# Driver4portas.net
KiCad netlist of a schematic drawn in EAGLE
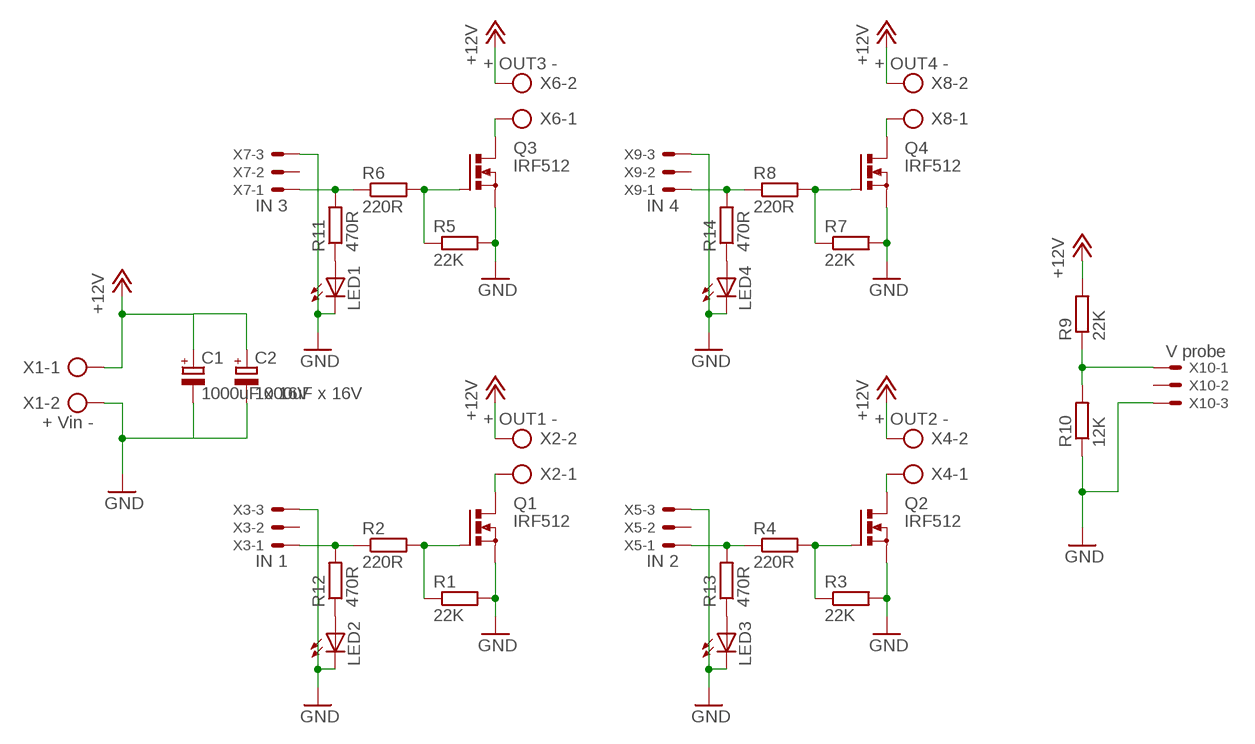
[diagram p0: schematic, sheet 1]

(export (version "E")
  (design (tool "Eeschema 10.0.6"))
  (components
    (comp (ref "C1")
      (value "1000uF x 16V")
      (footprint "eagle-import:E2,5-7")
      (libsource (lib "eagle-import") (part "CPOL-EUE2.5-7"))
    )
    (comp (ref "C2")
      (value "1000uF x 16V")
      (footprint "eagle-import:E2,5-7")
      (libsource (lib "eagle-import") (part "CPOL-EUE2.5-7"))
    )
    (comp (ref "LED1")
      (value "LED3MM")
      (footprint "eagle-import:LED3MM")
      (libsource (lib "eagle-import") (part "LED3MM"))
    )
    (comp (ref "LED2")
      (value "LED3MM")
      (footprint "eagle-import:LED3MM")
      (libsource (lib "eagle-import") (part "LED3MM"))
    )
    (comp (ref "LED3")
      (value "LED3MM")
      (footprint "eagle-import:LED3MM")
      (libsource (lib "eagle-import") (part "LED3MM"))
    )
    (comp (ref "LED4")
      (value "LED3MM")
      (footprint "eagle-import:LED3MM")
      (libsource (lib "eagle-import") (part "LED3MM"))
    )
    (comp (ref "Q1")
      (value "IRF512")
      (footprint "eagle-import:TO220BV")
      (libsource (lib "eagle-import") (part "IRF512"))
    )
    (comp (ref "Q2")
      (value "IRF512")
      (footprint "eagle-import:TO220BV")
      (libsource (lib "eagle-import") (part "IRF512"))
    )
    (comp (ref "Q3")
      (value "IRF512")
      (footprint "eagle-import:TO220BV")
      (libsource (lib "eagle-import") (part "IRF512"))
    )
    (comp (ref "Q4")
      (value "IRF512")
      (footprint "eagle-import:TO220BV")
      (libsource (lib "eagle-import") (part "IRF512"))
    )
    (comp (ref "R1")
      (value "22K")
      (footprint "eagle-import:0204_7")
      (libsource (lib "eagle-import") (part "R-EU_0204/7"))
    )
    (comp (ref "R2")
      (value "220R")
      (footprint "eagle-import:0204_7")
      (libsource (lib "eagle-import") (part "R-EU_0204/7"))
    )
    (comp (ref "R3")
      (value "22K")
      (footprint "eagle-import:0204_7")
      (libsource (lib "eagle-import") (part "R-EU_0204/7"))
    )
    (comp (ref "R4")
      (value "220R")
      (footprint "eagle-import:0204_7")
      (libsource (lib "eagle-import") (part "R-EU_0204/7"))
    )
    (comp (ref "R5")
      (value "22K")
      (footprint "eagle-import:0204_7")
      (libsource (lib "eagle-import") (part "R-EU_0204/7"))
    )
    (comp (ref "R6")
      (value "220R")
      (footprint "eagle-import:0204_7")
      (libsource (lib "eagle-import") (part "R-EU_0204/7"))
    )
    (comp (ref "R7")
      (value "22K")
      (footprint "eagle-import:0204_7")
      (libsource (lib "eagle-import") (part "R-EU_0204/7"))
    )
    (comp (ref "R8")
      (value "220R")
      (footprint "eagle-import:0204_7")
      (libsource (lib "eagle-import") (part "R-EU_0204/7"))
    )
    (comp (ref "R9")
      (value "22K")
      (footprint "eagle-import:0204_7")
      (libsource (lib "eagle-import") (part "R-EU_0204/7"))
    )
    (comp (ref "R10")
      (value "12K")
      (footprint "eagle-import:0204_7")
      (libsource (lib "eagle-import") (part "R-EU_0204/7"))
    )
    (comp (ref "R11")
      (value "470R")
      (footprint "eagle-import:0204V")
      (libsource (lib "eagle-import") (part "R-EU_0204/2V"))
    )
    (comp (ref "R12")
      (value "470R")
      (footprint "eagle-import:0204V")
      (libsource (lib "eagle-import") (part "R-EU_0204/2V"))
    )
    (comp (ref "R13")
      (value "470R")
      (footprint "eagle-import:0204V")
      (libsource (lib "eagle-import") (part "R-EU_0204/2V"))
    )
    (comp (ref "R14")
      (value "470R")
      (footprint "eagle-import:0204V")
      (libsource (lib "eagle-import") (part "R-EU_0204/2V"))
    )
    (comp (ref "X1")
      (value "+ Vin -")
      (footprint "eagle-import:AK500_2")
      (libsource (lib "eagle-import") (part "AK500/2"))
    )
    (comp (ref "X2")
      (value "+ OUT1 -")
      (footprint "eagle-import:AK500_2")
      (libsource (lib "eagle-import") (part "AK500/2"))
    )
    (comp (ref "X3")
      (value "IN 1")
      (footprint "eagle-import:22-23-2031")
      (fields (field (name "MF") "MOLEX") (field (name "MPN") "22-23-2031"))
      (libsource (lib "eagle-import") (part "22-23-2031"))
    )
    (comp (ref "X4")
      (value "+ OUT2 -")
      (footprint "eagle-import:AK500_2")
      (libsource (lib "eagle-import") (part "AK500/2"))
    )
    (comp (ref "X5")
      (value "IN 2")
      (footprint "eagle-import:22-23-2031")
      (fields (field (name "MF") "MOLEX") (field (name "MPN") "22-23-2031"))
      (libsource (lib "eagle-import") (part "22-23-2031"))
    )
    (comp (ref "X6")
      (value "+ OUT3 -")
      (footprint "eagle-import:AK500_2")
      (libsource (lib "eagle-import") (part "AK500/2"))
    )
    (comp (ref "X7")
      (value "IN 3")
      (footprint "eagle-import:22-23-2031")
      (fields (field (name "MF") "MOLEX") (field (name "MPN") "22-23-2031"))
      (libsource (lib "eagle-import") (part "22-23-2031"))
    )
    (comp (ref "X8")
      (value "+ OUT4 -")
      (footprint "eagle-import:AK500_2")
      (libsource (lib "eagle-import") (part "AK500/2"))
    )
    (comp (ref "X9")
      (value "IN 4")
      (footprint "eagle-import:22-23-2031")
      (fields (field (name "MF") "MOLEX") (field (name "MPN") "22-23-2031"))
      (libsource (lib "eagle-import") (part "22-23-2031"))
    )
    (comp (ref "X10")
      (value "V probe")
      (footprint "eagle-import:22-23-2031")
      (fields (field (name "MF") "MOLEX") (field (name "MPN") "22-23-2031"))
      (libsource (lib "eagle-import") (part "22-23-2031"))
    )
  )
  (nets
    (net (code "1") (name "+12V") (class "Default")
      (node (ref "C1") (pin "+") (pinfunction "+_+") (pintype "passive"))
      (node (ref "C2") (pin "+") (pinfunction "+_+") (pintype "passive"))
      (node (ref "R9") (pin "2") (pinfunction "2_2") (pintype "passive"))
      (node (ref "X1") (pin "1") (pinfunction "KL_1") (pintype "passive"))
      (node (ref "X2") (pin "2") (pinfunction "KL_2") (pintype "passive"))
      (node (ref "X4") (pin "2") (pinfunction "KL_2") (pintype "passive"))
      (node (ref "X6") (pin "2") (pinfunction "KL_2") (pintype "passive"))
      (node (ref "X8") (pin "2") (pinfunction "KL_2") (pintype "passive"))
    )
    (net (code "2") (name "GND") (class "Default")
      (node (ref "C1") (pin "-") (pinfunction "-_-") (pintype "passive"))
      (node (ref "C2") (pin "-") (pinfunction "-_-") (pintype "passive"))
      (node (ref "LED1") (pin "K") (pinfunction "C_K") (pintype "passive"))
      (node (ref "LED2") (pin "K") (pinfunction "C_K") (pintype "passive"))
      (node (ref "LED3") (pin "K") (pinfunction "C_K") (pintype "passive"))
      (node (ref "LED4") (pin "K") (pinfunction "C_K") (pintype "passive"))
      (node (ref "Q1") (pin "S") (pinfunction "S_S") (pintype "passive"))
      (node (ref "Q2") (pin "S") (pinfunction "S_S") (pintype "passive"))
      (node (ref "Q3") (pin "S") (pinfunction "S_S") (pintype "passive"))
      (node (ref "Q4") (pin "S") (pinfunction "S_S") (pintype "passive"))
      (node (ref "R1") (pin "2") (pinfunction "2_2") (pintype "passive"))
      (node (ref "R10") (pin "1") (pinfunction "1_1") (pintype "passive"))
      (node (ref "R3") (pin "2") (pinfunction "2_2") (pintype "passive"))
      (node (ref "R5") (pin "2") (pinfunction "2_2") (pintype "passive"))
      (node (ref "R7") (pin "2") (pinfunction "2_2") (pintype "passive"))
      (node (ref "X1") (pin "2") (pinfunction "KL_2") (pintype "passive"))
      (node (ref "X10") (pin "3") (pinfunction "S_3") (pintype "passive"))
      (node (ref "X3") (pin "3") (pinfunction "S_3") (pintype "passive"))
      (node (ref "X5") (pin "3") (pinfunction "S_3") (pintype "passive"))
      (node (ref "X7") (pin "3") (pinfunction "S_3") (pintype "passive"))
      (node (ref "X9") (pin "3") (pinfunction "S_3") (pintype "passive"))
    )
    (net (code "3") (name "Net-(LED1-PadA)") (class "Default")
      (node (ref "LED1") (pin "A") (pinfunction "A_A") (pintype "passive"))
      (node (ref "R11") (pin "1") (pinfunction "1_1") (pintype "passive"))
    )
    (net (code "4") (name "Net-(LED2-PadA)") (class "Default")
      (node (ref "LED2") (pin "A") (pinfunction "A_A") (pintype "passive"))
      (node (ref "R12") (pin "1") (pinfunction "1_1") (pintype "passive"))
    )
    (net (code "5") (name "Net-(LED3-PadA)") (class "Default")
      (node (ref "LED3") (pin "A") (pinfunction "A_A") (pintype "passive"))
      (node (ref "R13") (pin "1") (pinfunction "1_1") (pintype "passive"))
    )
    (net (code "6") (name "Net-(LED4-PadA)") (class "Default")
      (node (ref "LED4") (pin "A") (pinfunction "A_A") (pintype "passive"))
      (node (ref "R14") (pin "1") (pinfunction "1_1") (pintype "passive"))
    )
    (net (code "7") (name "Net-(Q1-PadG)") (class "Default")
      (node (ref "Q1") (pin "G") (pinfunction "G_G") (pintype "passive"))
      (node (ref "R1") (pin "1") (pinfunction "1_1") (pintype "passive"))
      (node (ref "R2") (pin "2") (pinfunction "2_2") (pintype "passive"))
    )
    (net (code "8") (name "Net-(Q2-PadG)") (class "Default")
      (node (ref "Q2") (pin "G") (pinfunction "G_G") (pintype "passive"))
      (node (ref "R3") (pin "1") (pinfunction "1_1") (pintype "passive"))
      (node (ref "R4") (pin "2") (pinfunction "2_2") (pintype "passive"))
    )
    (net (code "9") (name "Net-(Q3-PadG)") (class "Default")
      (node (ref "Q3") (pin "G") (pinfunction "G_G") (pintype "passive"))
      (node (ref "R5") (pin "1") (pinfunction "1_1") (pintype "passive"))
      (node (ref "R6") (pin "2") (pinfunction "2_2") (pintype "passive"))
    )
    (net (code "10") (name "Net-(Q4-PadG)") (class "Default")
      (node (ref "Q4") (pin "G") (pinfunction "G_G") (pintype "passive"))
      (node (ref "R7") (pin "1") (pinfunction "1_1") (pintype "passive"))
      (node (ref "R8") (pin "2") (pinfunction "2_2") (pintype "passive"))
    )
    (net (code "11") (name "Net-(X2A-KL)") (class "Default")
      (node (ref "Q1") (pin "D") (pinfunction "D_D") (pintype "passive"))
      (node (ref "X2") (pin "1") (pinfunction "KL_1") (pintype "passive"))
    )
    (net (code "12") (name "Net-(X3A-S)") (class "Default")
      (node (ref "R12") (pin "2") (pinfunction "2_2") (pintype "passive"))
      (node (ref "R2") (pin "1") (pinfunction "1_1") (pintype "passive"))
      (node (ref "X3") (pin "1") (pinfunction "S_1") (pintype "passive"))
    )
    (net (code "13") (name "Net-(X4A-KL)") (class "Default")
      (node (ref "Q2") (pin "D") (pinfunction "D_D") (pintype "passive"))
      (node (ref "X4") (pin "1") (pinfunction "KL_1") (pintype "passive"))
    )
    (net (code "14") (name "Net-(X5A-S)") (class "Default")
      (node (ref "R13") (pin "2") (pinfunction "2_2") (pintype "passive"))
      (node (ref "R4") (pin "1") (pinfunction "1_1") (pintype "passive"))
      (node (ref "X5") (pin "1") (pinfunction "S_1") (pintype "passive"))
    )
    (net (code "15") (name "Net-(X6A-KL)") (class "Default")
      (node (ref "Q3") (pin "D") (pinfunction "D_D") (pintype "passive"))
      (node (ref "X6") (pin "1") (pinfunction "KL_1") (pintype "passive"))
    )
    (net (code "16") (name "Net-(X7A-S)") (class "Default")
      (node (ref "R11") (pin "2") (pinfunction "2_2") (pintype "passive"))
      (node (ref "R6") (pin "1") (pinfunction "1_1") (pintype "passive"))
      (node (ref "X7") (pin "1") (pinfunction "S_1") (pintype "passive"))
    )
    (net (code "17") (name "Net-(X8A-KL)") (class "Default")
      (node (ref "Q4") (pin "D") (pinfunction "D_D") (pintype "passive"))
      (node (ref "X8") (pin "1") (pinfunction "KL_1") (pintype "passive"))
    )
    (net (code "18") (name "Net-(X9A-S)") (class "Default")
      (node (ref "R14") (pin "2") (pinfunction "2_2") (pintype "passive"))
      (node (ref "R8") (pin "1") (pinfunction "1_1") (pintype "passive"))
      (node (ref "X9") (pin "1") (pinfunction "S_1") (pintype "passive"))
    )
    (net (code "19") (name "Net-(X10A-S)") (class "Default")
      (node (ref "R10") (pin "2") (pinfunction "2_2") (pintype "passive"))
      (node (ref "R9") (pin "1") (pinfunction "1_1") (pintype "passive"))
      (node (ref "X10") (pin "1") (pinfunction "S_1") (pintype "passive"))
    )
    (net (code "20") (name "unconnected-(X3B-S-Pad2)") (class "Default")
      (node (ref "X3") (pin "2") (pinfunction "S_2") (pintype "passive"))
    )
    (net (code "21") (name "unconnected-(X5B-S-Pad2)") (class "Default")
      (node (ref "X5") (pin "2") (pinfunction "S_2") (pintype "passive"))
    )
    (net (code "22") (name "unconnected-(X7B-S-Pad2)") (class "Default")
      (node (ref "X7") (pin "2") (pinfunction "S_2") (pintype "passive"))
    )
    (net (code "23") (name "unconnected-(X9B-S-Pad2)") (class "Default")
      (node (ref "X9") (pin "2") (pinfunction "S_2") (pintype "passive"))
    )
    (net (code "24") (name "unconnected-(X10B-S-Pad2)") (class "Default")
      (node (ref "X10") (pin "2") (pinfunction "S_2") (pintype "passive"))
    )
  )
)
